# V-00780-01.net
KiCad netlist of a schematic drawn in EAGLE
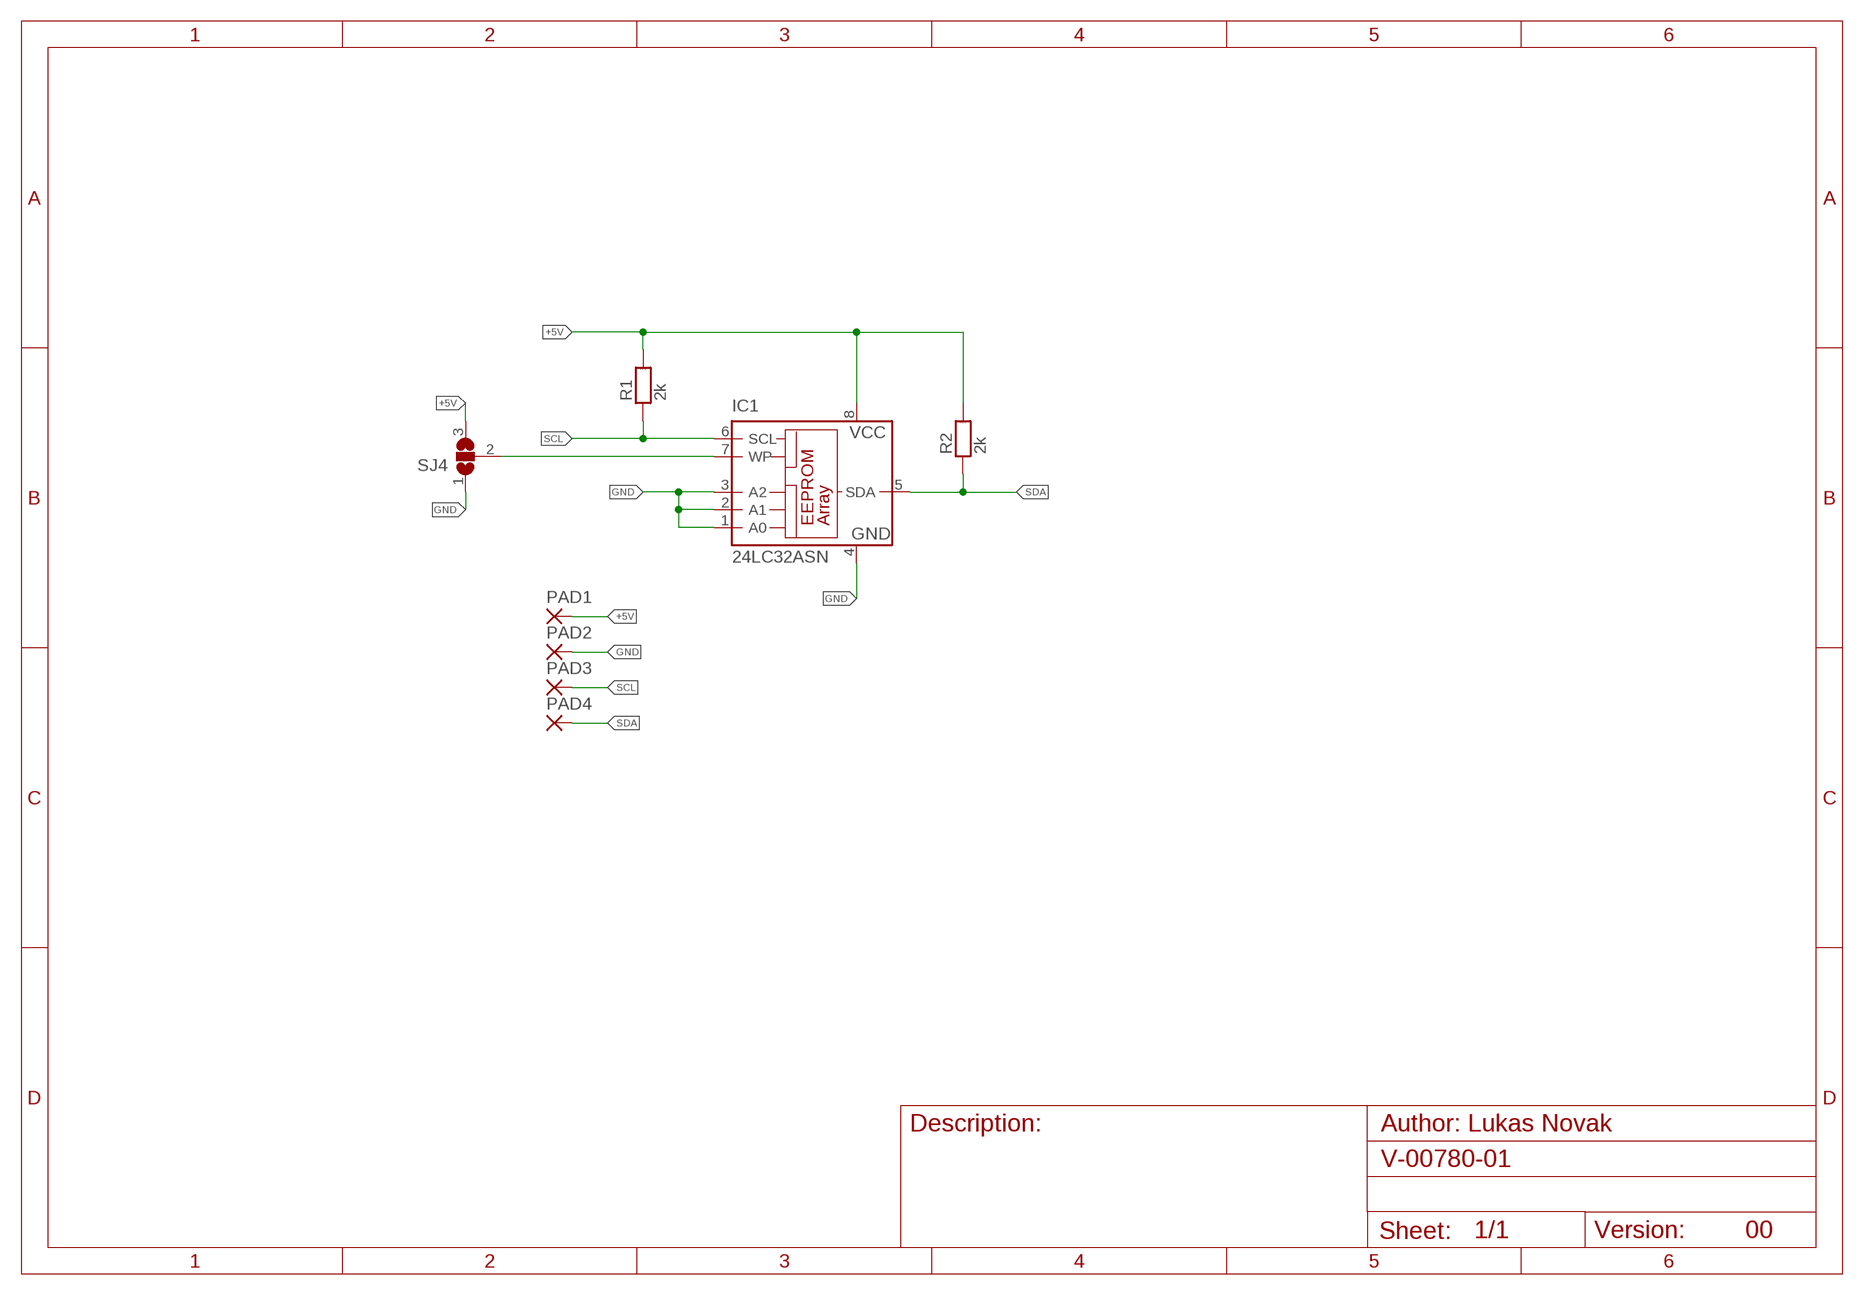
[diagram p0: schematic, sheet 1]

(export (version "E")
  (design (tool "Eeschema 10.0.6"))
  (components
    (comp (ref "IC1")
      (value "24LC32ASN")
      (footprint "eagle-import:SO-08")
      (fields (field (name "MF") "MICROCHIP") (field (name "MPN") "24LC32A/SN"))
      (libsource (lib "eagle-import") (part "24SNLC32A"))
    )
    (comp (ref "PAD1")
      (value "SMD2")
      (footprint "eagle-import:SMD1,27-2,54")
      (libsource (lib "eagle-import") (part "SMD2"))
    )
    (comp (ref "PAD2")
      (value "SMD2")
      (footprint "eagle-import:SMD1,27-2,54")
      (libsource (lib "eagle-import") (part "SMD2"))
    )
    (comp (ref "PAD3")
      (value "SMD2")
      (footprint "eagle-import:SMD1,27-2,54")
      (libsource (lib "eagle-import") (part "SMD2"))
    )
    (comp (ref "PAD4")
      (value "SMD2")
      (footprint "eagle-import:SMD1,27-2,54")
      (libsource (lib "eagle-import") (part "SMD2"))
    )
    (comp (ref "R1")
      (value "2k")
      (footprint "eagle-import:1206")
      (libsource (lib "eagle-import") (part "R_1206"))
    )
    (comp (ref "R2")
      (value "2k")
      (footprint "eagle-import:1206")
      (libsource (lib "eagle-import") (part "R_1206"))
    )
    (comp (ref "SJ4")
      (value "SJ2W")
      (footprint "eagle-import:SJ_2")
      (libsource (lib "eagle-import") (part "SJ2W"))
    )
  )
  (nets
    (net (code "1") (name "+5V") (class "Default")
      (node (ref "IC1") (pin "8") (pinfunction "VCC_8") (pintype "power_in"))
      (node (ref "PAD1") (pin "1") (pinfunction "P_1") (pintype "passive"))
      (node (ref "R1") (pin "2") (pinfunction "2_2") (pintype "passive"))
      (node (ref "R2") (pin "2") (pinfunction "2_2") (pintype "passive"))
      (node (ref "SJ4") (pin "3") (pinfunction "3_3") (pintype "passive"))
    )
    (net (code "2") (name "GND") (class "Default")
      (node (ref "IC1") (pin "1") (pinfunction "A0_1") (pintype "input"))
      (node (ref "IC1") (pin "2") (pinfunction "A1_2") (pintype "input"))
      (node (ref "IC1") (pin "3") (pinfunction "A2_3") (pintype "input"))
      (node (ref "IC1") (pin "4") (pinfunction "GND_4") (pintype "power_in"))
      (node (ref "PAD2") (pin "1") (pinfunction "P_1") (pintype "passive"))
      (node (ref "SJ4") (pin "1") (pinfunction "1_1") (pintype "passive"))
    )
    (net (code "3") (name "Net-(IC1-WP)") (class "Default")
      (node (ref "IC1") (pin "7") (pinfunction "WP_7") (pintype "input"))
      (node (ref "SJ4") (pin "2") (pinfunction "2_2") (pintype "passive"))
    )
    (net (code "4") (name "SCL") (class "Default")
      (node (ref "IC1") (pin "6") (pinfunction "SCL_6") (pintype "input"))
      (node (ref "PAD3") (pin "1") (pinfunction "P_1") (pintype "passive"))
      (node (ref "R1") (pin "1") (pinfunction "1_1") (pintype "passive"))
    )
    (net (code "5") (name "SDA") (class "Default")
      (node (ref "IC1") (pin "5") (pinfunction "SDA_5") (pintype "bidirectional"))
      (node (ref "PAD4") (pin "1") (pinfunction "P_1") (pintype "passive"))
      (node (ref "R2") (pin "1") (pinfunction "1_1") (pintype "passive"))
    )
  )
)
